# WINGS_SIGNAL_NODE_SCH.net
KiCad netlist of a schematic drawn in Altium Designer
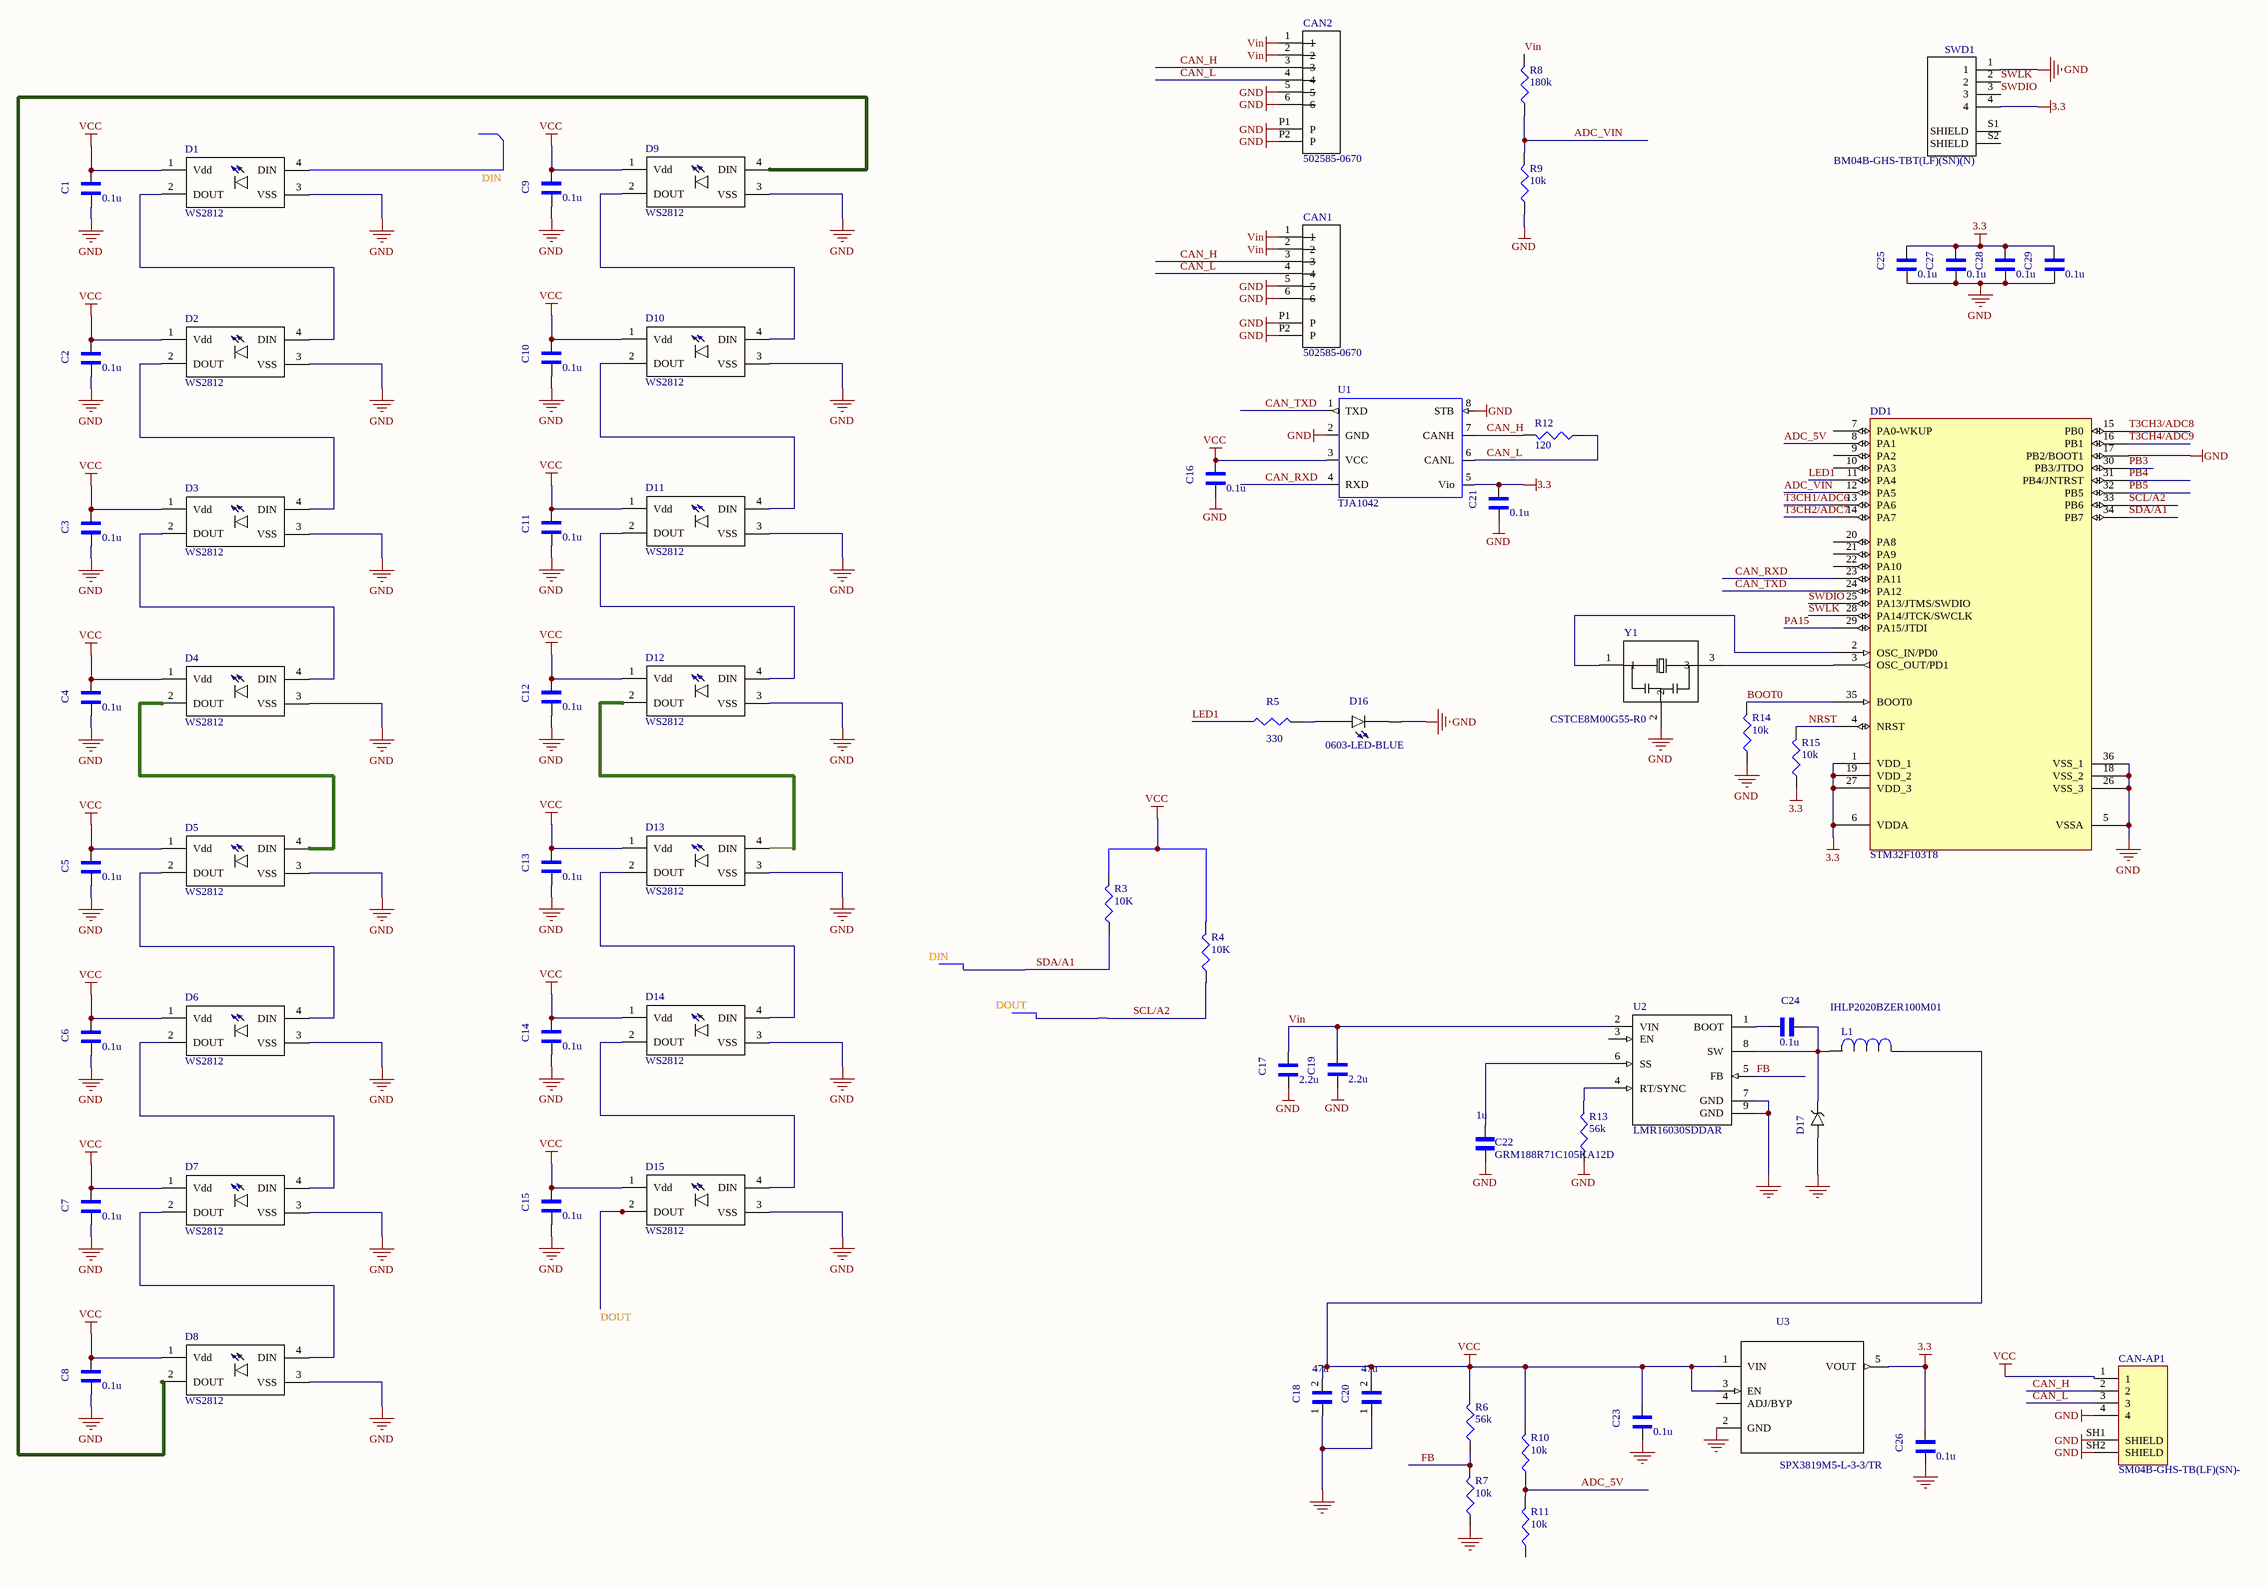
[diagram p0: WINGS_SIGNAL_NODE_SCH.SchDoc]

(export (version "E")
  (design (tool "Eeschema 10.0.6"))
  (components
    (comp (ref "C1")
      (value "0.1u")
      (footprint "*CAPC1608X90")
      (description "Cap Thin Film 0.1uf 50v 0603")
      (fields (field (name "MF") "AVX") (field (name "MP") "GX035C104MAT2-500 or CL10B104JB8NNNC"))
      (libsource (lib "lib") (part "GX035C104MAT2-500"))
    )
    (comp (ref "C2")
      (value "0.1u")
      (footprint "*CAPC1608X90")
      (description "Cap Thin Film 0.1uf 50v 0603")
      (fields (field (name "MF") "AVX") (field (name "MP") "GX035C104MAT2-500 or CL10B104JB8NNNC"))
      (libsource (lib "lib") (part "GX035C104MAT2-500"))
    )
    (comp (ref "C3")
      (value "0.1u")
      (footprint "*CAPC1608X90")
      (description "Cap Thin Film 0.1uf 50v 0603")
      (fields (field (name "MF") "AVX") (field (name "MP") "GX035C104MAT2-500 or CL10B104JB8NNNC"))
      (libsource (lib "lib") (part "GX035C104MAT2-500"))
    )
    (comp (ref "C4")
      (value "0.1u")
      (footprint "*CAPC1608X90")
      (description "Cap Thin Film 0.1uf 50v 0603")
      (fields (field (name "MF") "AVX") (field (name "MP") "GX035C104MAT2-500 or CL10B104JB8NNNC"))
      (libsource (lib "lib") (part "GX035C104MAT2-500"))
    )
    (comp (ref "C5")
      (value "0.1u")
      (footprint "*CAPC1608X90")
      (description "Cap Thin Film 0.1uf 50v 0603")
      (fields (field (name "MF") "AVX") (field (name "MP") "GX035C104MAT2-500 or CL10B104JB8NNNC"))
      (libsource (lib "lib") (part "GX035C104MAT2-500"))
    )
    (comp (ref "C6")
      (value "0.1u")
      (footprint "*CAPC1608X90")
      (description "Cap Thin Film 0.1uf 50v 0603")
      (fields (field (name "MF") "AVX") (field (name "MP") "GX035C104MAT2-500 or CL10B104JB8NNNC"))
      (libsource (lib "lib") (part "GX035C104MAT2-500"))
    )
    (comp (ref "C7")
      (value "0.1u")
      (footprint "*CAPC1608X90")
      (description "Cap Thin Film 0.1uf 50v 0603")
      (fields (field (name "MF") "AVX") (field (name "MP") "GX035C104MAT2-500 or CL10B104JB8NNNC"))
      (libsource (lib "lib") (part "GX035C104MAT2-500"))
    )
    (comp (ref "C8")
      (value "0.1u")
      (footprint "*CAPC1608X90")
      (description "Cap Thin Film 0.1uf 50v 0603")
      (fields (field (name "MF") "AVX") (field (name "MP") "GX035C104MAT2-500 or CL10B104JB8NNNC"))
      (libsource (lib "lib") (part "GX035C104MAT2-500"))
    )
    (comp (ref "C9")
      (value "0.1u")
      (footprint "*CAPC1608X90")
      (description "Cap Thin Film 0.1uf 50v 0603")
      (fields (field (name "MF") "AVX") (field (name "MP") "GX035C104MAT2-500 or CL10B104JB8NNNC"))
      (libsource (lib "lib") (part "GX035C104MAT2-500"))
    )
    (comp (ref "C10")
      (value "0.1u")
      (footprint "*CAPC1608X90")
      (description "Cap Thin Film 0.1uf 50v 0603")
      (fields (field (name "MF") "AVX") (field (name "MP") "GX035C104MAT2-500 or CL10B104JB8NNNC"))
      (libsource (lib "lib") (part "GX035C104MAT2-500"))
    )
    (comp (ref "C11")
      (value "0.1u")
      (footprint "*CAPC1608X90")
      (description "Cap Thin Film 0.1uf 50v 0603")
      (fields (field (name "MF") "AVX") (field (name "MP") "GX035C104MAT2-500 or CL10B104JB8NNNC"))
      (libsource (lib "lib") (part "GX035C104MAT2-500"))
    )
    (comp (ref "C12")
      (value "0.1u")
      (footprint "*CAPC1608X90")
      (description "Cap Thin Film 0.1uf 50v 0603")
      (fields (field (name "MF") "AVX") (field (name "MP") "GX035C104MAT2-500 or CL10B104JB8NNNC"))
      (libsource (lib "lib") (part "GX035C104MAT2-500"))
    )
    (comp (ref "C13")
      (value "0.1u")
      (footprint "*CAPC1608X90")
      (description "Cap Thin Film 0.1uf 50v 0603")
      (fields (field (name "MF") "AVX") (field (name "MP") "GX035C104MAT2-500 or CL10B104JB8NNNC"))
      (libsource (lib "lib") (part "GX035C104MAT2-500"))
    )
    (comp (ref "C14")
      (value "0.1u")
      (footprint "*CAPC1608X90")
      (description "Cap Thin Film 0.1uf 50v 0603")
      (fields (field (name "MF") "AVX") (field (name "MP") "GX035C104MAT2-500 or CL10B104JB8NNNC"))
      (libsource (lib "lib") (part "GX035C104MAT2-500"))
    )
    (comp (ref "C15")
      (value "0.1u")
      (footprint "*CAPC1608X90")
      (description "Cap Thin Film 0.1uf 50v 0603")
      (fields (field (name "MF") "AVX") (field (name "MP") "GX035C104MAT2-500 or CL10B104JB8NNNC"))
      (libsource (lib "lib") (part "GX035C104MAT2-500"))
    )
    (comp (ref "C16")
      (value "0.1u")
      (footprint "*CAPC1608X90")
      (description "Cap Thin Film 0.1uf 50v 0603")
      (fields (field (name "MF") "AVX") (field (name "MP") "GX035C104MAT2-500 or CL10B104JB8NNNC"))
      (libsource (lib "lib") (part "GX035C104MAT2-500"))
    )
    (comp (ref "C17")
      (value "2.2u")
      (footprint "*CAP3216X125N")
      (description "1206 2.2 uF 50 V В±10% Tolerance X7R SMT Multilayer Ceramic Capacitor")
      (fields (field (name "MF") "Murata Electronics") (field (name "MP") "GRM31CR71H225KA88L"))
      (libsource (lib "lib") (part "GRM31CR71H225KA88L"))
    )
    (comp (ref "C18")
      (value "47u")
      (footprint "*CAPC3216X125N")
      (description "Multilayer Ceramic Capacitor, GRM Series, 47 - F, - 10%, X5R, 10 V, 1206 [3216 Metric]")
      (fields (field (name "MF") "Murata Electronics") (field (name "MP") "GRM31CR61A476KE15L"))
      (libsource (lib "lib") (part "GRM31CR61A476KE15L"))
    )
    (comp (ref "C19")
      (value "2.2u")
      (footprint "*CAP3216X125N")
      (description "1206 2.2 uF 50 V В±10% Tolerance X7R SMT Multilayer Ceramic Capacitor")
      (fields (field (name "MF") "Murata Electronics") (field (name "MP") "GRM31CR71H225KA88L"))
      (libsource (lib "lib") (part "GRM31CR71H225KA88L"))
    )
    (comp (ref "C20")
      (value "47u")
      (footprint "*CAPC3216X125N")
      (description "Multilayer Ceramic Capacitor, GRM Series, 47 - F, - 10%, X5R, 10 V, 1206 [3216 Metric]")
      (fields (field (name "MF") "Murata Electronics") (field (name "MP") "GRM31CR61A476KE15L"))
      (libsource (lib "lib") (part "GRM31CR61A476KE15L"))
    )
    (comp (ref "C21")
      (value "0.1u")
      (footprint "*CAPC1608X90")
      (description "Cap Thin Film 0.1uf 50v 0603")
      (fields (field (name "MF") "AVX") (field (name "MP") "GX035C104MAT2-500 or CL10B104JB8NNNC"))
      (libsource (lib "lib") (part "GX035C104MAT2-500"))
    )
    (comp (ref "C22")
      (value "GRM188R71C105KA12D")
      (footprint "CAPC1608X90N")
      (description "SMD Capacitor X7R(EIA) with Capacitance: 1.0uF Tol. 10%. Rated Voltage: 16Vdc")
      (fields (field (name "MF") "Murata Electronics") (field (name "ALTIUM_VALUE") "1u"))
      (libsource (lib "lib") (part "GRM188R71C105KA12D"))
    )
    (comp (ref "C23")
      (value "0.1u")
      (footprint "*CAPC1608X90")
      (description "Cap Thin Film 0.1uf 50v 0603")
      (fields (field (name "MF") "AVX") (field (name "MP") "GX035C104MAT2-500"))
      (libsource (lib "lib") (part "GX035C104MAT2-500"))
    )
    (comp (ref "C24")
      (value "0.1u")
      (footprint "*CAPC1608X90")
      (description "Cap Thin Film 0.1uf 50v 0603")
      (fields (field (name "MF") "AVX") (field (name "MP") "GX035C104MAT2-500 or CL10B104JB8NNNC"))
      (libsource (lib "lib") (part "GX035C104MAT2-500"))
    )
    (comp (ref "C25")
      (value "0.1u")
      (footprint "*CAPC1608X90")
      (description "Cap Thin Film 0.1uf 50v 0603")
      (fields (field (name "MF") "AVX") (field (name "MP") "GX035C104MAT2-500 or CL10B104JB8NNNC"))
      (libsource (lib "lib") (part "GX035C104MAT2-500"))
    )
    (comp (ref "C26")
      (value "0.1u")
      (footprint "*CAPC1608X90")
      (description "Cap Thin Film 0.1uf 50v 0603")
      (fields (field (name "MF") "AVX") (field (name "MP") "GX035C104MAT2-500"))
      (libsource (lib "lib") (part "GX035C104MAT2-500"))
    )
    (comp (ref "C27")
      (value "0.1u")
      (footprint "*CAPC1608X90")
      (description "Cap Thin Film 0.1uf 50v 0603")
      (fields (field (name "MF") "AVX") (field (name "MP") "GX035C104MAT2-500 or CL10B104JB8NNNC"))
      (libsource (lib "lib") (part "GX035C104MAT2-500"))
    )
    (comp (ref "C28")
      (value "0.1u")
      (footprint "*CAPC1608X90")
      (description "Cap Thin Film 0.1uf 50v 0603")
      (fields (field (name "MF") "AVX") (field (name "MP") "GX035C104MAT2-500 or CL10B104JB8NNNC"))
      (libsource (lib "lib") (part "GX035C104MAT2-500"))
    )
    (comp (ref "C29")
      (value "0.1u")
      (footprint "*CAPC1608X90")
      (description "Cap Thin Film 0.1uf 50v 0603")
      (fields (field (name "MF") "AVX") (field (name "MP") "GX035C104MAT2-500 or CL10B104JB8NNNC"))
      (libsource (lib "lib") (part "GX035C104MAT2-500"))
    )
    (comp (ref "CAN-AP1")
      (value "SM04B-GHS-TB(LF)(SN)-")
      (footprint "JST_SM04B-GHS-TB(LF)(SN)-")
      (description "Connector Header Surface Mount, Right Angle 4 position 0.049 _1.25mm_")
      (fields (field (name "MP") "SM04B-GHS-TB(LF)(SN)") (field (name "MF") "JST Sales"))
      (libsource (lib "lib") (part "SM04B-GHS-TB(LF)(SN)-"))
    )
    (comp (ref "CAN1")
      (value "502585-0670")
      (footprint "MOLEX_502585-0670")
      (fields (field (name "MF") "Molex"))
      (libsource (lib "lib") (part "502585-0670"))
    )
    (comp (ref "CAN2")
      (value "502585-0670")
      (footprint "MOLEX_502585-0670")
      (fields (field (name "MF") "Molex"))
      (libsource (lib "lib") (part "502585-0670"))
    )
    (comp (ref "D1")
      (value "WS2812")
      (footprint "LED_WS2812")
      (description "Addressable Lighting - 5 LED Discrete Serial _Shift Register_ Red, Green, Blue _RGB_ 5.00mm Dia")
      (fields (field (name "MF") "SparkFun Electronics"))
      (libsource (lib "lib") (part "WS2812"))
    )
    (comp (ref "D2")
      (value "WS2812")
      (footprint "LED_WS2812")
      (description "Addressable Lighting - 5 LED Discrete Serial _Shift Register_ Red, Green, Blue _RGB_ 5.00mm Dia")
      (fields (field (name "MF") "SparkFun Electronics"))
      (libsource (lib "lib") (part "WS2812"))
    )
    (comp (ref "D3")
      (value "WS2812")
      (footprint "LED_WS2812")
      (description "Addressable Lighting - 5 LED Discrete Serial _Shift Register_ Red, Green, Blue _RGB_ 5.00mm Dia")
      (fields (field (name "MF") "SparkFun Electronics"))
      (libsource (lib "lib") (part "WS2812"))
    )
    (comp (ref "D4")
      (value "WS2812")
      (footprint "LED_WS2812")
      (description "Addressable Lighting - 5 LED Discrete Serial _Shift Register_ Red, Green, Blue _RGB_ 5.00mm Dia")
      (fields (field (name "MF") "SparkFun Electronics"))
      (libsource (lib "lib") (part "WS2812"))
    )
    (comp (ref "D5")
      (value "WS2812")
      (footprint "LED_WS2812")
      (description "Addressable Lighting - 5 LED Discrete Serial _Shift Register_ Red, Green, Blue _RGB_ 5.00mm Dia")
      (fields (field (name "MF") "SparkFun Electronics"))
      (libsource (lib "lib") (part "WS2812"))
    )
    (comp (ref "D6")
      (value "WS2812")
      (footprint "LED_WS2812")
      (description "Addressable Lighting - 5 LED Discrete Serial _Shift Register_ Red, Green, Blue _RGB_ 5.00mm Dia")
      (fields (field (name "MF") "SparkFun Electronics"))
      (libsource (lib "lib") (part "WS2812"))
    )
    (comp (ref "D7")
      (value "WS2812")
      (footprint "LED_WS2812")
      (description "Addressable Lighting - 5 LED Discrete Serial _Shift Register_ Red, Green, Blue _RGB_ 5.00mm Dia")
      (fields (field (name "MF") "SparkFun Electronics"))
      (libsource (lib "lib") (part "WS2812"))
    )
    (comp (ref "D8")
      (value "WS2812")
      (footprint "LED_WS2812")
      (description "Addressable Lighting - 5 LED Discrete Serial _Shift Register_ Red, Green, Blue _RGB_ 5.00mm Dia")
      (fields (field (name "MF") "SparkFun Electronics"))
      (libsource (lib "lib") (part "WS2812"))
    )
    (comp (ref "D9")
      (value "WS2812")
      (footprint "LED_WS2812")
      (description "Addressable Lighting - 5 LED Discrete Serial _Shift Register_ Red, Green, Blue _RGB_ 5.00mm Dia")
      (fields (field (name "MF") "SparkFun Electronics"))
      (libsource (lib "lib") (part "WS2812"))
    )
    (comp (ref "D10")
      (value "WS2812")
      (footprint "LED_WS2812")
      (description "Addressable Lighting - 5 LED Discrete Serial _Shift Register_ Red, Green, Blue _RGB_ 5.00mm Dia")
      (fields (field (name "MF") "SparkFun Electronics"))
      (libsource (lib "lib") (part "WS2812"))
    )
    (comp (ref "D11")
      (value "WS2812")
      (footprint "LED_WS2812")
      (description "Addressable Lighting - 5 LED Discrete Serial _Shift Register_ Red, Green, Blue _RGB_ 5.00mm Dia")
      (fields (field (name "MF") "SparkFun Electronics"))
      (libsource (lib "lib") (part "WS2812"))
    )
    (comp (ref "D12")
      (value "WS2812")
      (footprint "LED_WS2812")
      (description "Addressable Lighting - 5 LED Discrete Serial _Shift Register_ Red, Green, Blue _RGB_ 5.00mm Dia")
      (fields (field (name "MF") "SparkFun Electronics"))
      (libsource (lib "lib") (part "WS2812"))
    )
    (comp (ref "D13")
      (value "WS2812")
      (footprint "LED_WS2812")
      (description "Addressable Lighting - 5 LED Discrete Serial _Shift Register_ Red, Green, Blue _RGB_ 5.00mm Dia")
      (fields (field (name "MF") "SparkFun Electronics"))
      (libsource (lib "lib") (part "WS2812"))
    )
    (comp (ref "D14")
      (value "WS2812")
      (footprint "LED_WS2812")
      (description "Addressable Lighting - 5 LED Discrete Serial _Shift Register_ Red, Green, Blue _RGB_ 5.00mm Dia")
      (fields (field (name "MF") "SparkFun Electronics"))
      (libsource (lib "lib") (part "WS2812"))
    )
    (comp (ref "D15")
      (value "WS2812")
      (footprint "LED_WS2812")
      (description "Addressable Lighting - 5 LED Discrete Serial _Shift Register_ Red, Green, Blue _RGB_ 5.00mm Dia")
      (fields (field (name "MF") "SparkFun Electronics"))
      (libsource (lib "lib") (part "WS2812"))
    )
    (comp (ref "D16")
      (value "0603-LED-BLUE")
      (footprint "*LEDM1608X80_LTE-C1906R-14(Primary)")
      (description "LED IrLED Chip LED 2-Pin SMD T/R")
      (libsource (lib "lib") (part "LTE-C1906R-14"))
    )
    (comp (ref "D17")
      (value "SK56")
      (footprint "*SMB_P6SMB62AT3G(Primary)")
      (description "Диод Шоттки 5А 60В [SMB / DO-214AA]")
      (fields (field (name "MF") "Littelfuse Inc."))
      (libsource (lib "lib") (part "SK56"))
    )
    (comp (ref "DD1")
      (value "STM32F103T8")
      (footprint "*QFN50P600X600X100-37N")
      (description "STM32F103T8U6, Микроконтроллер 32BIT ARM 64K FLASH [VFQFPN-36]")
      (fields (field (name "MF") "STM") (field (name "MP") "STM32F103T8U6"))
      (libsource (lib "lib") (part "STM32F103T8"))
    )
    (comp (ref "L1")
      (value "IHLP2020BZER100M01")
      (footprint "IHLP")
      (description "10ÂµH Shielded Molded Inductor 2.3A 199mOhm Max Nonstandard")
      (fields (field (name "MF") "Vishay Dale"))
      (libsource (lib "lib") (part "IHLP2020BZER100M01"))
    )
    (comp (ref "R3")
      (value "10K")
      (footprint "J1-0603")
      (description "Resistor")
      (fields (field (name "MP") "4.7K 1% 0603") (field (name "Comment") "Res3"))
      (libsource (lib "Miscellaneous Devices") (part "Res3"))
    )
    (comp (ref "R4")
      (value "10K")
      (footprint "J1-0603")
      (description "Resistor")
      (fields (field (name "MP") "4.7K 1% 0603") (field (name "Comment") "Res3"))
      (libsource (lib "Miscellaneous Devices") (part "Res3"))
    )
    (comp (ref "R5")
      (value "330")
      (footprint "J1-0603")
      (description "Resistor")
      (fields (field (name "MP") "RC0603FR-07330RL") (field (name "Comment") "Res3"))
      (libsource (lib "Miscellaneous Devices") (part "Res3"))
    )
    (comp (ref "R6")
      (value "56k")
      (footprint "J1-0603")
      (description "Resistor")
      (fields (field (name "MP") "RC0603FR-0756KL") (field (name "Comment") "Res3"))
      (libsource (lib "Miscellaneous Devices") (part "Res3"))
    )
    (comp (ref "R7")
      (value "10k")
      (footprint "J1-0603")
      (description "10 kOhms 1 0.1 W 1 10 W Chip Resistor 0603 1608 Metric Thick Film")
      (fields (field (name "MF") "Yageo or NXP") (field (name "MP") "10K 1% 0603"))
      (libsource (lib "CAN_NODE_MINI") (part "RC0603FR-0710KL"))
    )
    (comp (ref "R8")
      (value "180k")
      (footprint "J1-0603")
      (description "Resistor")
      (fields (field (name "MP") "180K 1% 0603") (field (name "Comment") "Res3"))
      (libsource (lib "Miscellaneous Devices") (part "Res3"))
    )
    (comp (ref "R9")
      (value "10k")
      (footprint "J1-0603")
      (description "Resistor")
      (fields (field (name "MP") "10K 1% 0603") (field (name "Comment") "Res3"))
      (libsource (lib "Miscellaneous Devices") (part "Res3"))
    )
    (comp (ref "R10")
      (value "10k")
      (footprint "J1-0603")
      (description "10 kOhms 1 0.1 W 1 10 W Chip Resistor 0603 1608 Metric Thick Film")
      (fields (field (name "MF") "Yageo or NXP") (field (name "MP") "10K 1% 0603"))
      (libsource (lib "CAN_NODE_MINI") (part "RC0603FR-0710KL"))
    )
    (comp (ref "R11")
      (value "10k")
      (footprint "J1-0603")
      (description "10 kOhms 1 0.1 W 1 10 W Chip Resistor 0603 1608 Metric Thick Film")
      (fields (field (name "MF") "Yageo or NXP") (field (name "MP") "10K 1% 0603"))
      (libsource (lib "CAN_NODE_MINI") (part "RC0603FR-0710KL"))
    )
    (comp (ref "R12")
      (value "120")
      (footprint "J1-0603")
      (description "120 Ohms 1 0.1 W 1 10 W Chip Resistor 0603 1608 Metric Thick Film")
      (fields (field (name "MP") "RC0603FR-07120RL") (field (name "Comment") "Res3"))
      (libsource (lib "Miscellaneous Devices") (part "Res3"))
    )
    (comp (ref "R13")
      (value "56k")
      (footprint "J1-0603")
      (description "Resistor")
      (fields (field (name "MP") "RC0603FR-0756KL") (field (name "Comment") "Res3"))
      (libsource (lib "Miscellaneous Devices") (part "Res3"))
    )
    (comp (ref "R14")
      (value "10k")
      (footprint "J1-0603")
      (description "10 kOhms 1 0.1 W 1 10 W Chip Resistor 0603 1608 Metric Thick Film")
      (fields (field (name "MF") "Yageo or NXP") (field (name "MP") "10K 1% 0603"))
      (libsource (lib "CAN_NODE_MINI") (part "RC0603FR-0710KL"))
    )
    (comp (ref "R15")
      (value "10k")
      (footprint "J1-0603")
      (description "10 kOhms 1 0.1 W 1 10 W Chip Resistor 0603 1608 Metric Thick Film")
      (fields (field (name "MF") "Yageo or NXP") (field (name "MP") "10K 1% 0603"))
      (libsource (lib "CAN_NODE_MINI") (part "RC0603FR-0710KL"))
    )
    (comp (ref "SWD1")
      (value "BM04B-GHS-TBT(LF)(SN)(N)")
      (footprint "JST_BM04B-GHS-holes")
      (description "Conn Shrouded Header HDR 4 POS 1.25mm Solder ST SMD Reel")
      (fields (field (name "MF") "JST Sales") (field (name "MP") "SM04B-GHS-TB(LF)(SN)"))
      (libsource (lib "lib") (part "BM04B-GHS-TBT(LF)(SN)(N)"))
    )
    (comp (ref "U1")
      (value "TJA1042")
      (footprint "SOT782-1")
      (description "1/1 Transceiver Half CANbus 8-SO")
      (fields (field (name "MF") "NXP USA"))
      (libsource (lib "lib") (part "TJA1042"))
    )
    (comp (ref "U2")
      (value "LMR16030SDDAR")
      (footprint "*SOIC127P600X170-9N - duplicate")
      (fields (field (name "MF") "Texas Instruments"))
      (libsource (lib "lib") (part "LMR16030SDDAR"))
    )
    (comp (ref "U3")
      (value "SPX3819M5-L-3-3/TR")
      (footprint "*SOT95P280X145-5N")
      (description "Low Dropout Voltage Regulator, Adjustable 0.5A, В±1%, 2.5 to 16 Vin, 5-Pin SOT-23")
      (fields (field (name "MF") "MaxLinear, Inc."))
      (libsource (lib "DC_DC") (part "SPX3819M5-L"))
    )
    (comp (ref "Y1")
      (value "CSTCE8M00G55-R0")
      (footprint "*OSC_CSTCE8M00G55-R0")
      (description "Ceramic Resonator 8MHz ??0.5% _Tol_ ??0.2% _Stability_ 33pF 40Ohm 3-Pin CSMD T/R")
      (fields (field (name "MF") "Murata"))
      (libsource (lib "DC_DC") (part "CSTCE8M00G55-R0"))
    )
  )
  (nets
    (net (code "1") (name "/ADC_5V") (class "Default")
      (node (ref "DD1") (pin "8") (pinfunction "PA1_8") (pintype "bidirectional"))
      (node (ref "R10") (pin "1") (pinfunction "1_1") (pintype "passive"))
      (node (ref "R11") (pin "2") (pinfunction "2_2") (pintype "passive"))
    )
    (net (code "2") (name "/ADC_VIN") (class "Default")
      (node (ref "DD1") (pin "12") (pinfunction "PA5_12") (pintype "bidirectional"))
      (node (ref "R8") (pin "1") (pinfunction "1_1") (pintype "passive"))
      (node (ref "R9") (pin "2") (pinfunction "2_2") (pintype "passive"))
    )
    (net (code "3") (name "/BOOT0") (class "Default")
      (node (ref "DD1") (pin "35") (pinfunction "BOOT0_35") (pintype "input"))
      (node (ref "R14") (pin "2") (pinfunction "2_2") (pintype "passive"))
    )
    (net (code "4") (name "/CAN_H") (class "Default")
      (node (ref "CAN-AP1") (pin "2") (pinfunction "2_2") (pintype "passive"))
      (node (ref "CAN1") (pin "3") (pinfunction "3_3") (pintype "passive"))
      (node (ref "CAN2") (pin "3") (pinfunction "3_3") (pintype "passive"))
      (node (ref "R12") (pin "2") (pinfunction "2_2") (pintype "passive"))
      (node (ref "U1") (pin "7") (pinfunction "CANH_7") (pintype "bidirectional"))
    )
    (net (code "5") (name "/CAN_L") (class "Default")
      (node (ref "CAN-AP1") (pin "3") (pinfunction "3_3") (pintype "passive"))
      (node (ref "CAN1") (pin "4") (pinfunction "4_4") (pintype "passive"))
      (node (ref "CAN2") (pin "4") (pinfunction "4_4") (pintype "passive"))
      (node (ref "R12") (pin "1") (pinfunction "1_1") (pintype "passive"))
      (node (ref "U1") (pin "6") (pinfunction "CANL_6") (pintype "bidirectional"))
    )
    (net (code "6") (name "/CAN_RXD") (class "Default")
      (node (ref "DD1") (pin "23") (pinfunction "PA11_23") (pintype "bidirectional"))
      (node (ref "U1") (pin "4") (pinfunction "RXD_4") (pintype "bidirectional"))
    )
    (net (code "7") (name "/CAN_TXD") (class "Default")
      (node (ref "DD1") (pin "24") (pinfunction "PA12_24") (pintype "bidirectional"))
      (node (ref "U1") (pin "1") (pinfunction "TXD_1") (pintype "output"))
    )
    (net (code "8") (name "/DIN") (class "Default")
      (node (ref "D1") (pin "4") (pinfunction "DIN_4") (pintype "power_in"))
      (node (ref "DD1") (pin "34") (pinfunction "PB7_34") (pintype "bidirectional"))
      (node (ref "R3") (pin "1") (pinfunction "1_1") (pintype "passive"))
    )
    (net (code "9") (name "/DOUT") (class "Default")
      (node (ref "D15") (pin "2") (pinfunction "DOUT_2") (pintype "power_in"))
      (node (ref "DD1") (pin "33") (pinfunction "PB6_33") (pintype "bidirectional"))
      (node (ref "R4") (pin "1") (pinfunction "1_1") (pintype "passive"))
    )
    (net (code "10") (name "/FB") (class "Default")
      (node (ref "R6") (pin "1") (pinfunction "1_1") (pintype "passive"))
      (node (ref "R7") (pin "2") (pinfunction "2_2") (pintype "passive"))
      (node (ref "U2") (pin "5") (pinfunction "FB_5") (pintype "input"))
    )
    (net (code "11") (name "/LED1") (class "Default")
      (node (ref "DD1") (pin "11") (pinfunction "PA4_11") (pintype "bidirectional"))
      (node (ref "R5") (pin "1") (pinfunction "1_1") (pintype "passive"))
    )
    (net (code "12") (name "/NRST") (class "Default")
      (node (ref "DD1") (pin "4") (pinfunction "NRST_4") (pintype "bidirectional"))
      (node (ref "R15") (pin "2") (pinfunction "2_2") (pintype "passive"))
    )
    (net (code "13") (name "/PA15") (class "Default")
      (node (ref "DD1") (pin "29") (pinfunction "PA15/JTDI_29") (pintype "bidirectional"))
    )
    (net (code "14") (name "/PB3") (class "Default")
      (node (ref "DD1") (pin "30") (pinfunction "PB3/JTDO_30") (pintype "bidirectional"))
    )
    (net (code "15") (name "/PB4") (class "Default")
      (node (ref "DD1") (pin "31") (pinfunction "PB4/JNTRST_31") (pintype "bidirectional"))
    )
    (net (code "16") (name "/PB5") (class "Default")
      (node (ref "DD1") (pin "32") (pinfunction "PB5_32") (pintype "bidirectional"))
    )
    (net (code "17") (name "/SWDIO") (class "Default")
      (node (ref "DD1") (pin "25") (pinfunction "PA13/JTMS/SWDIO_25") (pintype "bidirectional"))
      (node (ref "SWD1") (pin "3") (pinfunction "3_3") (pintype "passive"))
    )
    (net (code "18") (name "/SWLK") (class "Default")
      (node (ref "DD1") (pin "28") (pinfunction "PA14/JTCK/SWCLK_28") (pintype "bidirectional"))
      (node (ref "SWD1") (pin "2") (pinfunction "2_2") (pintype "passive"))
    )
    (net (code "19") (name "/T3CH1{slash}ADC6") (class "Default")
      (node (ref "DD1") (pin "13") (pinfunction "PA6_13") (pintype "bidirectional"))
    )
    (net (code "20") (name "/T3CH2{slash}ADC7") (class "Default")
      (node (ref "DD1") (pin "14") (pinfunction "PA7_14") (pintype "bidirectional"))
    )
    (net (code "21") (name "/T3CH3{slash}ADC8") (class "Default")
      (node (ref "DD1") (pin "15") (pinfunction "PB0_15") (pintype "bidirectional"))
    )
    (net (code "22") (name "/T3CH4{slash}ADC9") (class "Default")
      (node (ref "DD1") (pin "16") (pinfunction "PB1_16") (pintype "bidirectional"))
    )
    (net (code "23") (name "3.3") (class "Default")
      (node (ref "C21") (pin "1") (pinfunction "1_1") (pintype "passive"))
      (node (ref "C25") (pin "1") (pinfunction "1_1") (pintype "passive"))
      (node (ref "C26") (pin "1") (pinfunction "1_1") (pintype "passive"))
      (node (ref "C27") (pin "1") (pinfunction "1_1") (pintype "passive"))
      (node (ref "C28") (pin "1") (pinfunction "1_1") (pintype "passive"))
      (node (ref "C29") (pin "1") (pinfunction "1_1") (pintype "passive"))
      (node (ref "DD1") (pin "1") (pinfunction "VDD_1_1") (pintype "power_in"))
      (node (ref "DD1") (pin "19") (pinfunction "VDD_2_19") (pintype "power_in"))
      (node (ref "DD1") (pin "27") (pinfunction "VDD_3_27") (pintype "power_in"))
      (node (ref "DD1") (pin "6") (pinfunction "VDDA_6") (pintype "power_in"))
      (node (ref "R15") (pin "1") (pinfunction "1_1") (pintype "passive"))
      (node (ref "SWD1") (pin "4") (pinfunction "4_4") (pintype "passive"))
      (node (ref "U1") (pin "5") (pinfunction "Vio_5") (pintype "power_in"))
      (node (ref "U3") (pin "5") (pinfunction "VOUT_5") (pintype "output"))
    )
    (net (code "24") (name "GND") (class "Default")
      (node (ref "C1") (pin "2") (pinfunction "2_2") (pintype "passive"))
      (node (ref "C10") (pin "2") (pinfunction "2_2") (pintype "passive"))
      (node (ref "C11") (pin "2") (pinfunction "2_2") (pintype "passive"))
      (node (ref "C12") (pin "2") (pinfunction "2_2") (pintype "passive"))
      (node (ref "C13") (pin "2") (pinfunction "2_2") (pintype "passive"))
      (node (ref "C14") (pin "2") (pinfunction "2_2") (pintype "passive"))
      (node (ref "C15") (pin "2") (pinfunction "2_2") (pintype "passive"))
      (node (ref "C16") (pin "2") (pinfunction "2_2") (pintype "passive"))
      (node (ref "C17") (pin "2") (pinfunction "2_2") (pintype "passive"))
      (node (ref "C18") (pin "1") (pinfunction "1_1") (pintype "passive"))
      (node (ref "C19") (pin "2") (pinfunction "2_2") (pintype "passive"))
      (node (ref "C2") (pin "2") (pinfunction "2_2") (pintype "passive"))
      (node (ref "C20") (pin "1") (pinfunction "1_1") (pintype "passive"))
      (node (ref "C21") (pin "2") (pinfunction "2_2") (pintype "passive"))
      (node (ref "C22") (pin "1") (pinfunction "1_1") (pintype "passive"))
      (node (ref "C23") (pin "2") (pinfunction "2_2") (pintype "passive"))
      (node (ref "C25") (pin "2") (pinfunction "2_2") (pintype "passive"))
      (node (ref "C26") (pin "2") (pinfunction "2_2") (pintype "passive"))
      (node (ref "C27") (pin "2") (pinfunction "2_2") (pintype "passive"))
      (node (ref "C28") (pin "2") (pinfunction "2_2") (pintype "passive"))
      (node (ref "C29") (pin "2") (pinfunction "2_2") (pintype "passive"))
      (node (ref "C3") (pin "2") (pinfunction "2_2") (pintype "passive"))
      (node (ref "C4") (pin "2") (pinfunction "2_2") (pintype "passive"))
      (node (ref "C5") (pin "2") (pinfunction "2_2") (pintype "passive"))
      (node (ref "C6") (pin "2") (pinfunction "2_2") (pintype "passive"))
      (node (ref "C7") (pin "2") (pinfunction "2_2") (pintype "passive"))
      (node (ref "C8") (pin "2") (pinfunction "2_2") (pintype "passive"))
      (node (ref "C9") (pin "2") (pinfunction "2_2") (pintype "passive"))
      (node (ref "CAN-AP1") (pin "4") (pinfunction "4_4") (pintype "passive"))
      (node (ref "CAN-AP1") (pin "SH1") (pinfunction "SHIELD_SH1") (pintype "power_in"))
      (node (ref "CAN-AP1") (pin "SH2") (pinfunction "SHIELD_SH2") (pintype "power_in"))
      (node (ref "CAN1") (pin "5") (pinfunction "5_5") (pintype "passive"))
      (node (ref "CAN1") (pin "6") (pinfunction "6_6") (pintype "passive"))
      (node (ref "CAN1") (pin "P1") (pinfunction "P_P1") (pintype "passive"))
      (node (ref "CAN1") (pin "P2") (pinfunction "P_P2") (pintype "passive"))
      (node (ref "CAN2") (pin "5") (pinfunction "5_5") (pintype "passive"))
      (node (ref "CAN2") (pin "6") (pinfunction "6_6") (pintype "passive"))
      (node (ref "CAN2") (pin "P1") (pinfunction "P_P1") (pintype "passive"))
      (node (ref "CAN2") (pin "P2") (pinfunction "P_P2") (pintype "passive"))
      (node (ref "D1") (pin "3") (pinfunction "VSS_3") (pintype "power_in"))
      (node (ref "D10") (pin "3") (pinfunction "VSS_3") (pintype "power_in"))
      (node (ref "D11") (pin "3") (pinfunction "VSS_3") (pintype "power_in"))
      (node (ref "D12") (pin "3") (pinfunction "VSS_3") (pintype "power_in"))
      (node (ref "D13") (pin "3") (pinfunction "VSS_3") (pintype "power_in"))
      (node (ref "D14") (pin "3") (pinfunction "VSS_3") (pintype "power_in"))
      (node (ref "D15") (pin "3") (pinfunction "VSS_3") (pintype "power_in"))
      (node (ref "D16") (pin "C") (pinfunction "C_C") (pintype "passive"))
      (node (ref "D17") (pin "A") (pinfunction "A_A") (pintype "power_in"))
      (node (ref "D2") (pin "3") (pinfunction "VSS_3") (pintype "power_in"))
      (node (ref "D3") (pin "3") (pinfunction "VSS_3") (pintype "power_in"))
      (node (ref "D4") (pin "3") (pinfunction "VSS_3") (pintype "power_in"))
      (node (ref "D5") (pin "3") (pinfunction "VSS_3") (pintype "power_in"))
      (node (ref "D6") (pin "3") (pinfunction "VSS_3") (pintype "power_in"))
      (node (ref "D7") (pin "3") (pinfunction "VSS_3") (pintype "power_in"))
      (node (ref "D8") (pin "3") (pinfunction "VSS_3") (pintype "power_in"))
      (node (ref "D9") (pin "3") (pinfunction "VSS_3") (pintype "power_in"))
      (node (ref "DD1") (pin "17") (pinfunction "PB2/BOOT1_17") (pintype "bidirectional"))
      (node (ref "DD1") (pin "18") (pinfunction "VSS_2_18") (pintype "power_in"))
      (node (ref "DD1") (pin "26") (pinfunction "VSS_3_26") (pintype "power_in"))
      (node (ref "DD1") (pin "36") (pinfunction "VSS_1_36") (pintype "power_in"))
      (node (ref "DD1") (pin "5") (pinfunction "VSSA_5") (pintype "power_in"))
      (node (ref "R13") (pin "1") (pinfunction "1_1") (pintype "passive"))
      (node (ref "R14") (pin "1") (pinfunction "1_1") (pintype "passive"))
      (node (ref "R7") (pin "1") (pinfunction "1_1") (pintype "passive"))
      (node (ref "R9") (pin "1") (pinfunction "1_1") (pintype "passive"))
      (node (ref "SWD1") (pin "1") (pinfunction "1_1") (pintype "passive"))
      (node (ref "U1") (pin "2") (pinfunction "GND_2") (pintype "power_in"))
      (node (ref "U1") (pin "8") (pinfunction "STB_8") (pintype "input"))
      (node (ref "U2") (pin "7") (pinfunction "GND_7") (pintype "power_in"))
      (node (ref "U2") (pin "9") (pinfunction "GND_9") (pintype "power_in"))
      (node (ref "U3") (pin "2") (pinfunction "GND_2") (pintype "passive"))
      (node (ref "Y1") (pin "2") (pinfunction "2_2") (pintype "power_in"))
    )
    (net (code "25") (name "Net-(D1-DOUT)") (class "Default")
      (node (ref "D1") (pin "2") (pinfunction "DOUT_2") (pintype "power_in"))
      (node (ref "D2") (pin "4") (pinfunction "DIN_4") (pintype "power_in"))
    )
    (net (code "26") (name "Net-(D2-DOUT)") (class "Default")
      (node (ref "D2") (pin "2") (pinfunction "DOUT_2") (pintype "power_in"))
      (node (ref "D3") (pin "4") (pinfunction "DIN_4") (pintype "power_in"))
    )
    (net (code "27") (name "Net-(D3-DOUT)") (class "Default")
      (node (ref "D3") (pin "2") (pinfunction "DOUT_2") (pintype "power_in"))
      (node (ref "D4") (pin "4") (pinfunction "DIN_4") (pintype "power_in"))
    )
    (net (code "28") (name "Net-(D4-DOUT)") (class "Default")
      (node (ref "D4") (pin "2") (pinfunction "DOUT_2") (pintype "power_in"))
      (node (ref "D5") (pin "4") (pinfunction "DIN_4") (pintype "power_in"))
    )
    (net (code "29") (name "Net-(D5-DOUT)") (class "Default")
      (node (ref "D5") (pin "2") (pinfunction "DOUT_2") (pintype "power_in"))
      (node (ref "D6") (pin "4") (pinfunction "DIN_4") (pintype "power_in"))
    )
    (net (code "30") (name "Net-(D6-DOUT)") (class "Default")
      (node (ref "D6") (pin "2") (pinfunction "DOUT_2") (pintype "power_in"))
      (node (ref "D7") (pin "4") (pinfunction "DIN_4") (pintype "power_in"))
    )
    (net (code "31") (name "Net-(D7-DOUT)") (class "Default")
      (node (ref "D7") (pin "2") (pinfunction "DOUT_2") (pintype "power_in"))
      (node (ref "D8") (pin "4") (pinfunction "DIN_4") (pintype "power_in"))
    )
    (net (code "32") (name "Net-(D8-DOUT)") (class "Default")
      (node (ref "D8") (pin "2") (pinfunction "DOUT_2") (pintype "power_in"))
      (node (ref "D9") (pin "4") (pinfunction "DIN_4") (pintype "power_in"))
    )
    (net (code "33") (name "Net-(D10-DIN)") (class "Default")
      (node (ref "D10") (pin "4") (pinfunction "DIN_4") (pintype "power_in"))
      (node (ref "D9") (pin "2") (pinfunction "DOUT_2") (pintype "power_in"))
    )
    (net (code "34") (name "Net-(D10-DOUT)") (class "Default")
      (node (ref "D10") (pin "2") (pinfunction "DOUT_2") (pintype "power_in"))
      (node (ref "D11") (pin "4") (pinfunction "DIN_4") (pintype "power_in"))
    )
    (net (code "35") (name "Net-(D11-DOUT)") (class "Default")
      (node (ref "D11") (pin "2") (pinfunction "DOUT_2") (pintype "power_in"))
      (node (ref "D12") (pin "4") (pinfunction "DIN_4") (pintype "power_in"))
    )
    (net (code "36") (name "Net-(D12-DOUT)") (class "Default")
      (node (ref "D12") (pin "2") (pinfunction "DOUT_2") (pintype "power_in"))
      (node (ref "D13") (pin "4") (pinfunction "DIN_4") (pintype "power_in"))
    )
    (net (code "37") (name "Net-(D13-DOUT)") (class "Default")
      (node (ref "D13") (pin "2") (pinfunction "DOUT_2") (pintype "power_in"))
      (node (ref "D14") (pin "4") (pinfunction "DIN_4") (pintype "power_in"))
    )
    (net (code "38") (name "Net-(D14-DOUT)") (class "Default")
      (node (ref "D14") (pin "2") (pinfunction "DOUT_2") (pintype "power_in"))
      (node (ref "D15") (pin "4") (pinfunction "DIN_4") (pintype "power_in"))
    )
    (net (code "39") (name "Net-(D16-PadA)") (class "Default")
      (node (ref "D16") (pin "A") (pinfunction "A_A") (pintype "passive"))
      (node (ref "R5") (pin "2") (pinfunction "2_2") (pintype "passive"))
    )
    (net (code "40") (name "Net-(DD1-OSC_IN{slash}PD0)") (class "Default")
      (node (ref "DD1") (pin "2") (pinfunction "OSC_IN/PD0_2") (pintype "input"))
      (node (ref "Y1") (pin "1") (pinfunction "1_1") (pintype "passive"))
    )
    (net (code "41") (name "Net-(DD1-OSC_OUT{slash}PD1)") (class "Default")
      (node (ref "DD1") (pin "3") (pinfunction "OSC_OUT/PD1_3") (pintype "output"))
      (node (ref "Y1") (pin "3") (pinfunction "3_3") (pintype "passive"))
    )
    (net (code "42") (name "Net-(U2-BOOT)") (class "Default")
      (node (ref "C24") (pin "2") (pinfunction "2_2") (pintype "passive"))
      (node (ref "U2") (pin "1") (pinfunction "BOOT_1") (pintype "power_in"))
    )
    (net (code "43") (name "Net-(U2-RT{slash}SYNC)") (class "Default")
      (node (ref "R13") (pin "2") (pinfunction "2_2") (pintype "passive"))
      (node (ref "U2") (pin "4") (pinfunction "RT/SYNC_4") (pintype "input"))
    )
    (net (code "44") (name "Net-(U2-SS)") (class "Default")
      (node (ref "C22") (pin "2") (pinfunction "2_2") (pintype "passive"))
      (node (ref "U2") (pin "6") (pinfunction "SS_6") (pintype "input"))
    )
    (net (code "45") (name "Net-(U2-SW)") (class "Default")
      (node (ref "C24") (pin "1") (pinfunction "1_1") (pintype "passive"))
      (node (ref "D17") (pin "C") (pinfunction "C_C") (pintype "power_in"))
      (node (ref "L1") (pin "2") (pinfunction "2_2") (pintype "passive"))
      (node (ref "U2") (pin "8") (pinfunction "SW_8") (pintype "power_in"))
    )
    (net (code "46") (name "VCC") (class "Default")
      (node (ref "C1") (pin "1") (pinfunction "1_1") (pintype "passive"))
      (node (ref "C10") (pin "1") (pinfunction "1_1") (pintype "passive"))
      (node (ref "C11") (pin "1") (pinfunction "1_1") (pintype "passive"))
      (node (ref "C12") (pin "1") (pinfunction "1_1") (pintype "passive"))
      (node (ref "C13") (pin "1") (pinfunction "1_1") (pintype "passive"))
      (node (ref "C14") (pin "1") (pinfunction "1_1") (pintype "passive"))
      (node (ref "C15") (pin "1") (pinfunction "1_1") (pintype "passive"))
      (node (ref "C16") (pin "1") (pinfunction "1_1") (pintype "passive"))
      (node (ref "C18") (pin "2") (pinfunction "2_2") (pintype "passive"))
      (node (ref "C2") (pin "1") (pinfunction "1_1") (pintype "passive"))
      (node (ref "C20") (pin "2") (pinfunction "2_2") (pintype "passive"))
      (node (ref "C23") (pin "1") (pinfunction "1_1") (pintype "passive"))
      (node (ref "C3") (pin "1") (pinfunction "1_1") (pintype "passive"))
      (node (ref "C4") (pin "1") (pinfunction "1_1") (pintype "passive"))
      (node (ref "C5") (pin "1") (pinfunction "1_1") (pintype "passive"))
      (node (ref "C6") (pin "1") (pinfunction "1_1") (pintype "passive"))
      (node (ref "C7") (pin "1") (pinfunction "1_1") (pintype "passive"))
      (node (ref "C8") (pin "1") (pinfunction "1_1") (pintype "passive"))
      (node (ref "C9") (pin "1") (pinfunction "1_1") (pintype "passive"))
      (node (ref "CAN-AP1") (pin "1") (pinfunction "1_1") (pintype "passive"))
      (node (ref "D1") (pin "1") (pinfunction "Vdd_1") (pintype "power_in"))
      (node (ref "D10") (pin "1") (pinfunction "Vdd_1") (pintype "power_in"))
      (node (ref "D11") (pin "1") (pinfunction "Vdd_1") (pintype "power_in"))
      (node (ref "D12") (pin "1") (pinfunction "Vdd_1") (pintype "power_in"))
      (node (ref "D13") (pin "1") (pinfunction "Vdd_1") (pintype "power_in"))
      (node (ref "D14") (pin "1") (pinfunction "Vdd_1") (pintype "power_in"))
      (node (ref "D15") (pin "1") (pinfunction "Vdd_1") (pintype "power_in"))
      (node (ref "D2") (pin "1") (pinfunction "Vdd_1") (pintype "power_in"))
      (node (ref "D3") (pin "1") (pinfunction "Vdd_1") (pintype "power_in"))
      (node (ref "D4") (pin "1") (pinfunction "Vdd_1") (pintype "power_in"))
      (node (ref "D5") (pin "1") (pinfunction "Vdd_1") (pintype "power_in"))
      (node (ref "D6") (pin "1") (pinfunction "Vdd_1") (pintype "power_in"))
      (node (ref "D7") (pin "1") (pinfunction "Vdd_1") (pintype "power_in"))
      (node (ref "D8") (pin "1") (pinfunction "Vdd_1") (pintype "power_in"))
      (node (ref "D9") (pin "1") (pinfunction "Vdd_1") (pintype "power_in"))
      (node (ref "L1") (pin "1") (pinfunction "1_1") (pintype "passive"))
      (node (ref "R10") (pin "2") (pinfunction "2_2") (pintype "passive"))
      (node (ref "R3") (pin "2") (pinfunction "2_2") (pintype "passive"))
      (node (ref "R4") (pin "2") (pinfunction "2_2") (pintype "passive"))
      (node (ref "R6") (pin "2") (pinfunction "2_2") (pintype "passive"))
      (node (ref "U1") (pin "3") (pinfunction "VCC_3") (pintype "power_in"))
      (node (ref "U3") (pin "1") (pinfunction "VIN_1") (pintype "power_in"))
      (node (ref "U3") (pin "3") (pinfunction "EN_3") (pintype "input"))
    )
    (net (code "47") (name "Vin") (class "Default")
      (node (ref "C17") (pin "1") (pinfunction "1_1") (pintype "passive"))
      (node (ref "C19") (pin "1") (pinfunction "1_1") (pintype "passive"))
      (node (ref "CAN1") (pin "1") (pinfunction "1_1") (pintype "passive"))
      (node (ref "CAN1") (pin "2") (pinfunction "2_2") (pintype "passive"))
      (node (ref "CAN2") (pin "1") (pinfunction "1_1") (pintype "passive"))
      (node (ref "CAN2") (pin "2") (pinfunction "2_2") (pintype "passive"))
      (node (ref "R8") (pin "2") (pinfunction "2_2") (pintype "passive"))
      (node (ref "U2") (pin "2") (pinfunction "VIN_2") (pintype "power_in"))
    )
    (net (code "48") (name "unconnected-(DD1-PA0-WKUP-Pad7)") (class "Default")
      (node (ref "DD1") (pin "7") (pinfunction "PA0-WKUP_7") (pintype "bidirectional"))
    )
    (net (code "49") (name "unconnected-(DD1-PA2-Pad9)") (class "Default")
      (node (ref "DD1") (pin "9") (pinfunction "PA2_9") (pintype "bidirectional"))
    )
    (net (code "50") (name "unconnected-(DD1-PA3-Pad10)") (class "Default")
      (node (ref "DD1") (pin "10") (pinfunction "PA3_10") (pintype "bidirectional"))
    )
    (net (code "51") (name "unconnected-(DD1-PA8-Pad20)") (class "Default")
      (node (ref "DD1") (pin "20") (pinfunction "PA8_20") (pintype "bidirectional"))
    )
    (net (code "52") (name "unconnected-(DD1-PA9-Pad21)") (class "Default")
      (node (ref "DD1") (pin "21") (pinfunction "PA9_21") (pintype "bidirectional"))
    )
    (net (code "53") (name "unconnected-(DD1-PA10-Pad22)") (class "Default")
      (node (ref "DD1") (pin "22") (pinfunction "PA10_22") (pintype "bidirectional"))
    )
    (net (code "54") (name "unconnected-(R11-Pad1)") (class "Default")
      (node (ref "R11") (pin "1") (pinfunction "1_1") (pintype "passive"))
    )
    (net (code "55") (name "unconnected-(SWD1-SHIELD-PadS1)") (class "Default")
      (node (ref "SWD1") (pin "S1") (pinfunction "SHIELD_S1") (pintype "passive"))
    )
    (net (code "56") (name "unconnected-(SWD1-SHIELD-PadS2)") (class "Default")
      (node (ref "SWD1") (pin "S2") (pinfunction "SHIELD_S2") (pintype "passive"))
    )
    (net (code "57") (name "unconnected-(U2-EN-Pad3)") (class "Default")
      (node (ref "U2") (pin "3") (pinfunction "EN_3") (pintype "input"))
    )
    (net (code "58") (name "unconnected-(U3-ADJ{slash}BYP-Pad4)") (class "Default")
      (node (ref "U3") (pin "4") (pinfunction "ADJ/BYP_4") (pintype "passive"))
    )
  )
)
